# Arduino_Uno_Kit.net
KiCad netlist of a schematic drawn in Altium Designer
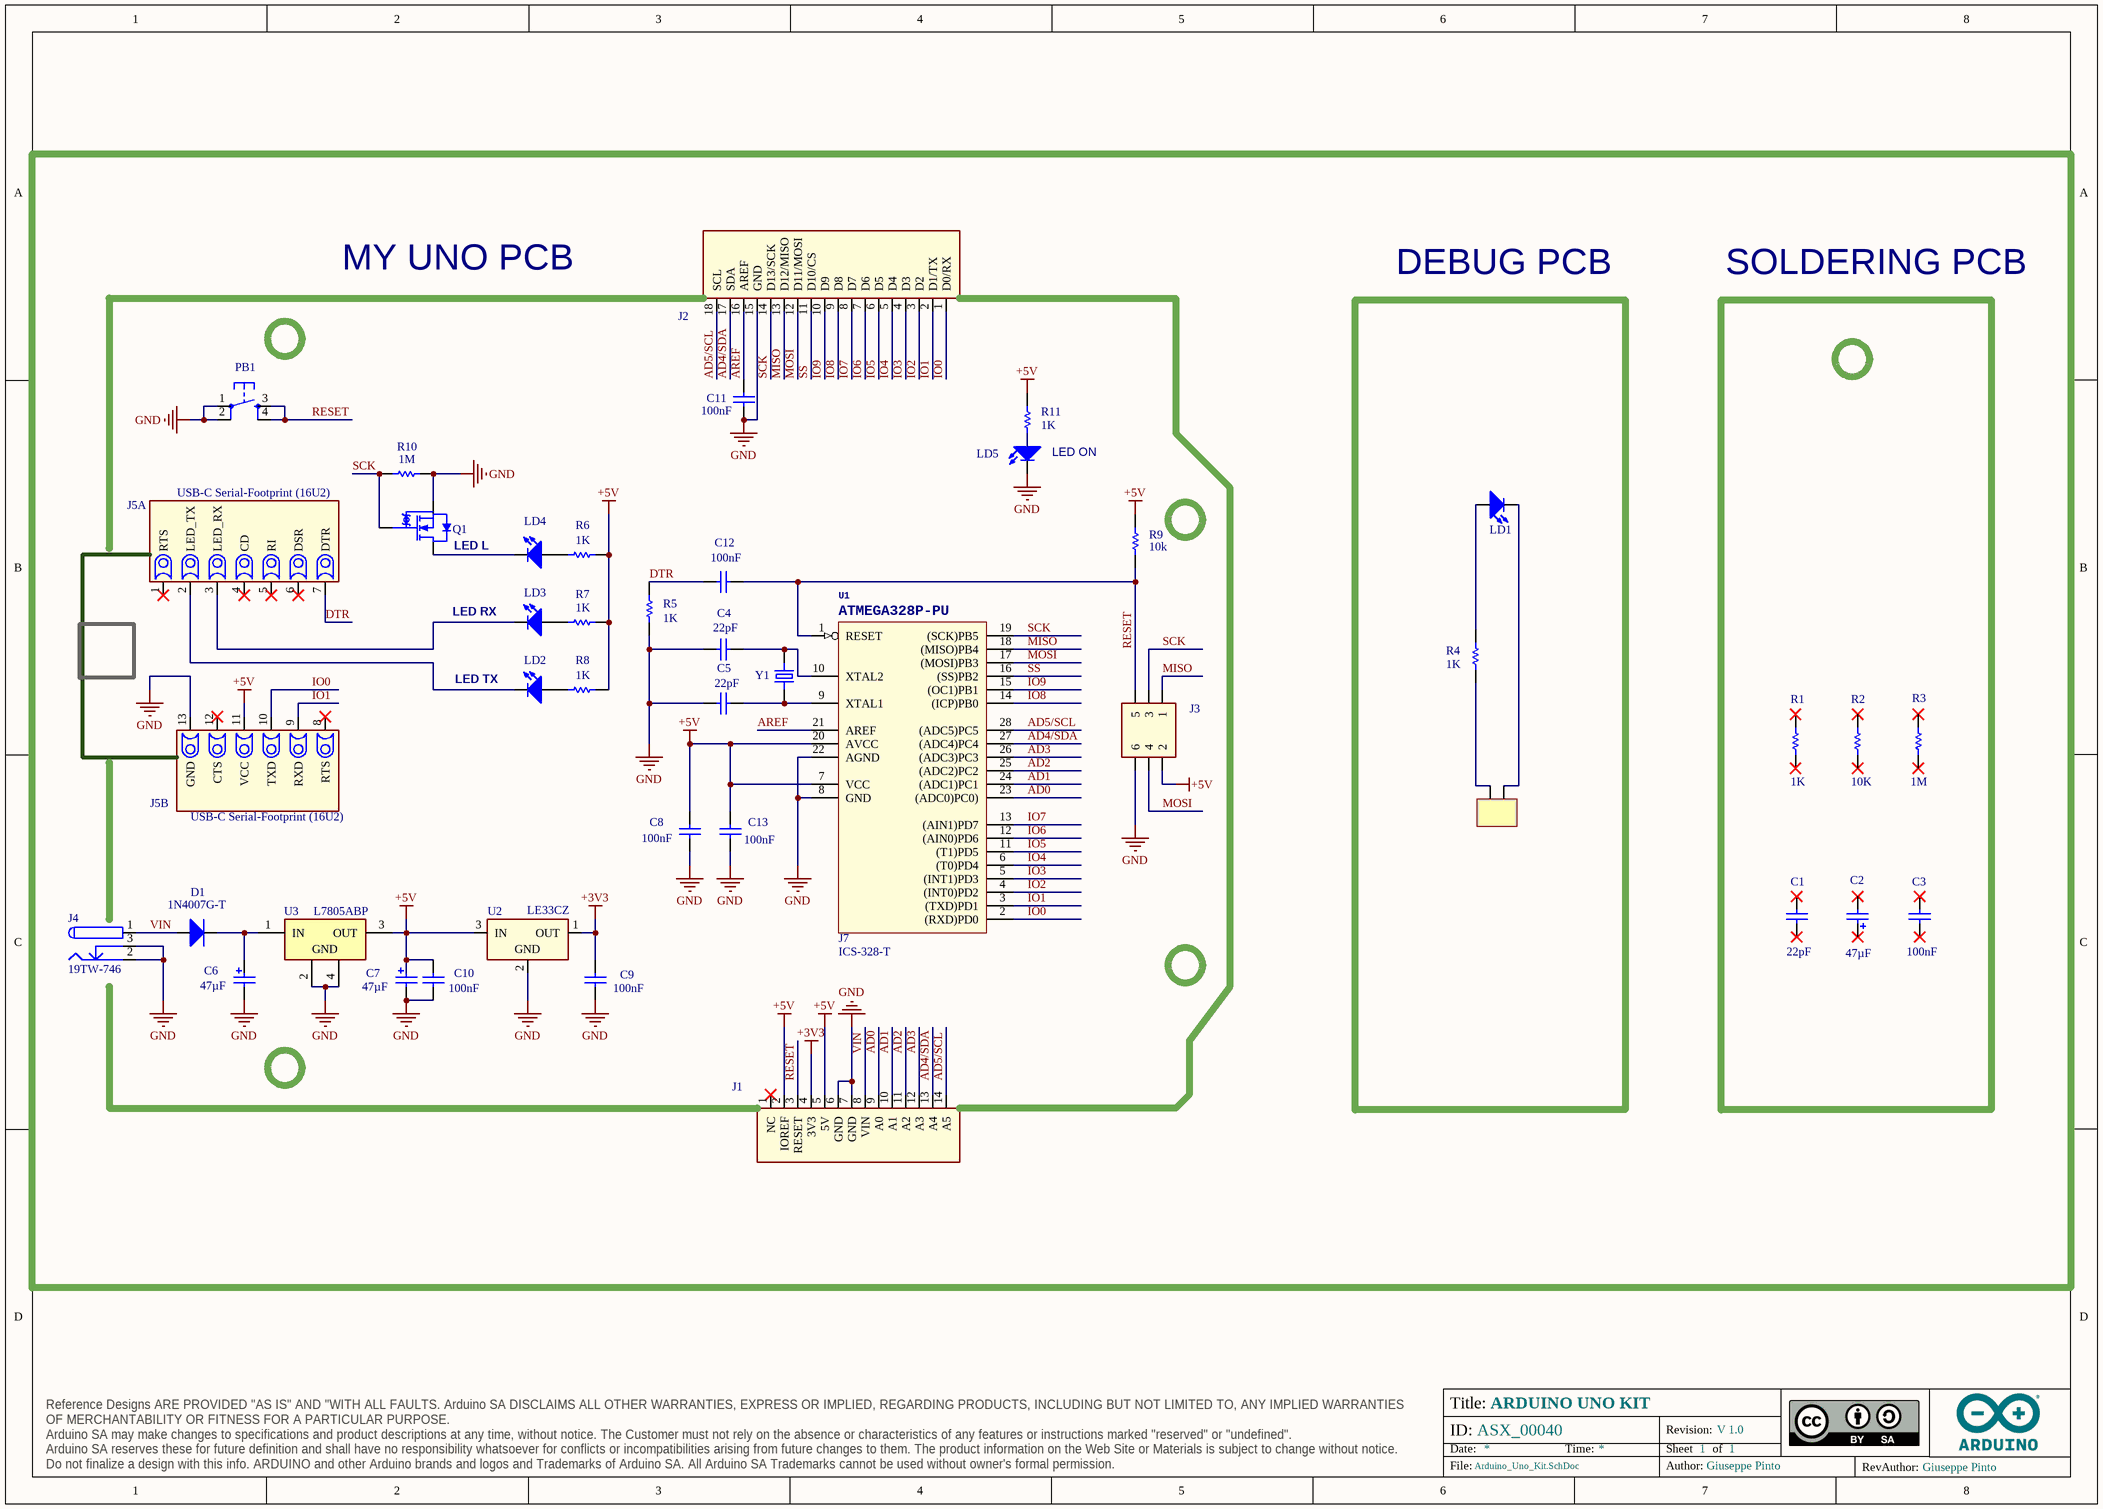
[diagram p0: Arduino_Uno_Kit.SchDoc]

(export (version "E")
  (design (tool "Eeschema 10.0.6"))
  (components
    (comp (ref "C1")
      (value "22pF")
      (footprint "TS170R1H220JSANB0R")
      (description "CAP THD 22pF 50V C0G 5%")
      (fields (field (name "PART NUMBER") "TS170R1H220JSANB0R") (field (name "MANUFACTURER") "Suntan"))
      (libsource (lib "Clean") (part "CAP"))
    )
    (comp (ref "C2")
      (value "47µF")
      (footprint "EKF476M1EE05TU")
      (description "CAP ALUM POL THD 47uF 25V")
      (fields (field (name "VOLTAGE") "25V") (field (name "PART NUMBER") "EKF476M1EE05TU"))
      (libsource (lib "Clean") (part "CAP-POL"))
    )
    (comp (ref "C3")
      (value "100nF")
      (footprint "B32529C0104J289")
      (description "CAP THD 100NF 63V POLIESTER")
      (fields (field (name "PART NUMBER") "B32529C0104J289") (field (name "MANUFACTURER") "EPCOS"))
      (libsource (lib "Clean") (part "CAP"))
    )
    (comp (ref "C4")
      (value "22pF")
      (footprint "TS170R1H220JSANB0R")
      (description "CAP THD 22pF 50V C0G 5%")
      (fields (field (name "PART NUMBER") "TS170R1H220JSANB0R") (field (name "MANUFACTURER") "Suntan"))
      (libsource (lib "Clean") (part "CAP"))
    )
    (comp (ref "C5")
      (value "22pF")
      (footprint "TS170R1H220JSANB0R")
      (description "CAP THD 22pF 50V C0G 5%")
      (fields (field (name "PART NUMBER") "TS170R1H220JSANB0R") (field (name "MANUFACTURER") "Suntan"))
      (libsource (lib "Clean") (part "CAP"))
    )
    (comp (ref "C6")
      (value "47µF")
      (footprint "EKF476M1EE05TU")
      (description "CAP ALUM POL THD 47uF 25V")
      (fields (field (name "VOLTAGE") "25V") (field (name "PART NUMBER") "EKF476M1EE05TU"))
      (libsource (lib "Clean") (part "CAP-POL"))
    )
    (comp (ref "C7")
      (value "47µF")
      (footprint "EKF476M1EE05TU")
      (description "CAP ALUM POL THD 47uF 25V")
      (fields (field (name "VOLTAGE") "25V") (field (name "PART NUMBER") "EKF476M1EE05TU"))
      (libsource (lib "Clean") (part "CAP-POL"))
    )
    (comp (ref "C8")
      (value "100nF")
      (footprint "B32529C0104J289")
      (description "CAP THD 100NF 63V POLIESTER")
      (fields (field (name "PART NUMBER") "B32529C0104J289") (field (name "MANUFACTURER") "EPCOS"))
      (libsource (lib "Clean") (part "CAP"))
    )
    (comp (ref "C9")
      (value "100nF")
      (footprint "B32529C0104J289")
      (description "CAP THD 100NF 63V POLIESTER")
      (fields (field (name "PART NUMBER") "B32529C0104J289") (field (name "MANUFACTURER") "EPCOS"))
      (libsource (lib "Clean") (part "CAP"))
    )
    (comp (ref "C10")
      (value "100nF")
      (footprint "B32529C0104J289")
      (description "CAP THD 100NF 63V POLIESTER")
      (fields (field (name "PART NUMBER") "B32529C0104J289") (field (name "MANUFACTURER") "EPCOS"))
      (libsource (lib "Clean") (part "CAP"))
    )
    (comp (ref "C11")
      (value "100nF")
      (footprint "B32529C0104J289")
      (description "CAP THD 100NF 63V POLIESTER")
      (fields (field (name "PART NUMBER") "B32529C0104J289") (field (name "MANUFACTURER") "EPCOS"))
      (libsource (lib "Clean") (part "CAP"))
    )
    (comp (ref "C12")
      (value "100nF")
      (footprint "B32529C0104J289")
      (description "CAP THD 100NF 63V POLIESTER")
      (fields (field (name "PART NUMBER") "B32529C0104J289") (field (name "MANUFACTURER") "EPCOS"))
      (libsource (lib "Clean") (part "CAP"))
    )
    (comp (ref "C13")
      (value "100nF")
      (footprint "B32529C0104J289")
      (description "CAP THD 100NF 63V POLIESTER")
      (fields (field (name "PART NUMBER") "B32529C0104J289") (field (name "MANUFACTURER") "EPCOS"))
      (libsource (lib "Clean") (part "CAP"))
    )
    (comp (ref "D1")
      (value "1N4007G-T")
      (footprint "1N4007G-T-Footprint-1")
      (description "Diodes [1N4007]")
      (fields (field (name "MANUFACTURER") "Panjit"))
      (libsource (lib "Clean") (part "1N4007G-T"))
    )
    (comp (ref "J1")
      (value "20TW-995")
      (footprint "1X14-CUSTOM")
      (description "CONN STRIP F/1/D 14v SER.NERA s1pin")
      (libsource (lib "Clean") (part "20TW-995"))
    )
    (comp (ref "J2")
      (value "20TW-994")
      (footprint "1X18-CUSTOM")
      (description "CONN STRIP F/1/D 18v SER.NERA s1pin")
      (libsource (lib "Clean") (part "20TW-994"))
    )
    (comp (ref "J3")
      (value "PH2-06-UA")
      (footprint "2X03")
      (description "CONN Header Through Hole 6 position 0.100\" (2.54mm)")
      (fields (field (name "MANUFACTURER") "Adam Tech"))
      (libsource (lib "Clean") (part "PH2-06-UA"))
    )
    (comp (ref "J4")
      (value "19TW-746")
      (footprint "POWERSUPPLY_DC-21MM")
      (description "CONN PWR JACK 2.1X5.5MM SOLDER")
      (fields (field (name "MANUFACTURER") "4UCON"))
      (libsource (lib "Clean") (part "19TW-746"))
    )
    (comp (ref "J5")
      (value "USB-C Serial-Footprint (16U2)")
      (footprint "USB-C Serial-Footprint (16U2)")
      (libsource (lib "Clean") (part "USB-C Serial CARRIER"))
    )
    (comp (ref "J6")
      (value "MK125002GO")
      (footprint "MK125002GO")
      (description "CONN MORS.CS 2v p3,5 10A aLING.VER")
      (fields (field (name "MANUFACTURER") "Adimpex"))
      (libsource (lib "Clean") (part "MK125002GO"))
    )
    (comp (ref "J7")
      (value "ICS-328-T")
      (footprint "ICS-328-T-Footprint-1")
      (description "CONN DIP 28 SOCKET")
      (fields (field (name "MANUFACTURER") "Adam Tech"))
      (libsource (lib "Clean") (part "CMP-003-0010-A.2"))
    )
    (comp (ref "LD1")
      (value "L-7104YD")
      (footprint "L314YD-Footprint-1")
      (description "LED THD YELLOW DIFFUSED T-1, 3mm")
      (fields (field (name "MANUFACTURER") "Kingbright"))
      (libsource (lib "Clean") (part "LED"))
    )
    (comp (ref "LD2")
      (value "L-7104YD")
      (footprint "L314YD-Footprint-1")
      (description "LED THD YELLOW DIFFUSED T-1, 3mm")
      (fields (field (name "MANUFACTURER") "Kingbright"))
      (libsource (lib "Clean") (part "LED"))
    )
    (comp (ref "LD3")
      (value "L-7104YD")
      (footprint "L314YD-Footprint-1")
      (description "LED THD YELLOW DIFFUSED T-1, 3mm")
      (fields (field (name "MANUFACTURER") "Kingbright"))
      (libsource (lib "Clean") (part "LED"))
    )
    (comp (ref "LD4")
      (value "L-7104YD")
      (footprint "L314YD-Footprint-1")
      (description "LED THD YELLOW DIFFUSED T-1, 3mm")
      (fields (field (name "MANUFACTURER") "Kingbright"))
      (libsource (lib "Clean") (part "LED"))
    )
    (comp (ref "LD5")
      (value "L-7104GD")
      (footprint "L314YD-Footprint-1")
      (description "LED THD GREEN DIFFUSED T-1, 3mm")
      (fields (field (name "MANUFACTURER") "Kingbright"))
      (libsource (lib "Clean") (part "LED"))
    )
    (comp (ref "PB1")
      (value "TS21043-160B-5227260")
      (footprint "SW6X6")
      (description "PUSHBUTTON.6x6 CS Hatt0,7 NERO 160g")
      (libsource (lib "Clean") (part "PB-TE"))
    )
    (comp (ref "Q1")
      (value "2N7000BU")
      (footprint "SOT23")
      (description "TRANSISTOR NMOS SMALL SIGNAL EFFECT 0.2A I(D) 1-ELEMENT")
      (fields (field (name "MANUFACTURER") "Onsemi"))
      (libsource (lib "Clean") (part "NMOS-2"))
    )
    (comp (ref "R1")
      (value "1K")
      (footprint "A5215")
      (description "RES FIXED THD 1K OHM 1/4W 5%")
      (fields (field (name "TOLERANCE") "5%") (field (name "POWER") "250mW"))
      (libsource (lib "Clean") (part "RES"))
    )
    (comp (ref "R2")
      (value "10K")
      (footprint "A5213")
      (description "RES THD 10K 1/4W 5%")
      (fields (field (name "TOLERANCE") "5%") (field (name "POWER") "250mW"))
      (libsource (lib "Clean") (part "RES"))
    )
    (comp (ref "R3")
      (value "1M")
      (footprint "A5217")
      (description "RES THD 1M OHM 1/4w  5%")
      (fields (field (name "TOLERANCE") "5%") (field (name "POWER") "250mW"))
      (libsource (lib "Clean") (part "RES"))
    )
    (comp (ref "R4")
      (value "1K")
      (footprint "A5215")
      (description "RES FIXED THD 1K OHM 1/4W 5%")
      (fields (field (name "TOLERANCE") "5%") (field (name "POWER") "250mW"))
      (libsource (lib "Clean") (part "RES"))
    )
    (comp (ref "R5")
      (value "1K")
      (footprint "A5215")
      (description "RES FIXED THD 1K OHM 1/4W 5%")
      (fields (field (name "TOLERANCE") "5%") (field (name "POWER") "250mW"))
      (libsource (lib "Clean") (part "RES"))
    )
    (comp (ref "R6")
      (value "1K")
      (footprint "A5215")
      (description "RES FIXED THD 1K OHM 1/4W 5%")
      (fields (field (name "TOLERANCE") "5%") (field (name "POWER") "250mW"))
      (libsource (lib "Clean") (part "RES"))
    )
    (comp (ref "R7")
      (value "1K")
      (footprint "A5215")
      (description "RES FIXED THD 1K OHM 1/4W 5%")
      (fields (field (name "TOLERANCE") "5%") (field (name "POWER") "250mW"))
      (libsource (lib "Clean") (part "RES"))
    )
    (comp (ref "R8")
      (value "1K")
      (footprint "A5215")
      (description "RES FIXED THD 1K OHM 1/4W 5%")
      (fields (field (name "TOLERANCE") "5%") (field (name "POWER") "250mW"))
      (libsource (lib "Clean") (part "RES"))
    )
    (comp (ref "R9")
      (value "10k")
      (footprint "A5213")
      (description "RES THD 10K 1/4W 5%")
      (fields (field (name "TOLERANCE") "5%") (field (name "POWER") "250mW"))
      (libsource (lib "Clean") (part "RES"))
    )
    (comp (ref "R10")
      (value "1M")
      (footprint "A5217")
      (description "RES THD 1M OHM 1/4w  5%")
      (fields (field (name "TOLERANCE") "5%") (field (name "POWER") "250mW"))
      (libsource (lib "Clean") (part "RES"))
    )
    (comp (ref "R11")
      (value "1K")
      (footprint "A5215")
      (description "RES FIXED THD 1K OHM 1/4W 5%")
      (fields (field (name "TOLERANCE") "5%") (field (name "POWER") "250mW"))
      (libsource (lib "Clean") (part "RES"))
    )
    (comp (ref "U1")
      (value "ATMEGA328P-PU")
      (footprint "DIL28-3")
      (description "IC MICROCONTROLLER ATMEGA328P-PU")
      (fields (field (name "MANUFACTURER") "Microchip"))
      (libsource (lib "Clean") (part "ATMEGA328P-PU-A.6"))
    )
    (comp (ref "U2")
      (value "LE33CZ")
      (footprint "LE33CZ-TR/AP")
      (description "IC REG LDO FIXED 3.3V, 0.2V DROPOUT TO-92-3")
      (fields (field (name "PART NUMBER") "LE33CZ-TR/AP") (field (name "MANUFACTURER") "STMicroelectronics"))
      (libsource (lib "Clean") (part "LE33CZ-TR/AP"))
    )
    (comp (ref "U3")
      (value "L7805ABP")
      (footprint "TO220")
      (description "IC REG LINEAR 5V 1.5A TO220AB")
      (fields (field (name "MANUFACTURER") "STMicroelectronics") (field (name "TOLERANCE") "5%"))
      (libsource (lib "Clean") (part "L7805CT"))
    )
    (comp (ref "Y1")
      (value "ECS-160-20-4X-DU")
      (footprint "ECS-160-20-4X-DU-Footprint-1")
      (description "CRYSTAL 16.0000MHZ 20PF THD")
      (fields (field (name "MANUFACTURER") "ECS"))
      (libsource (lib "Clean") (part "Crystal"))
    )
  )
  (nets
    (net (code "1") (name "+3V3") (class "Default")
      (node (ref "C9") (pin "1") (pinfunction "1_1") (pintype "passive"))
      (node (ref "J1") (pin "4") (pinfunction "3V3_4") (pintype "passive"))
      (node (ref "U2") (pin "1") (pinfunction "OUT_1") (pintype "power_in"))
    )
    (net (code "2") (name "+5V") (class "Default")
      (node (ref "C10") (pin "1") (pinfunction "1_1") (pintype "passive"))
      (node (ref "C13") (pin "1") (pinfunction "1_1") (pintype "passive"))
      (node (ref "C7") (pin "2") (pinfunction "2_2") (pintype "passive"))
      (node (ref "C8") (pin "1") (pinfunction "1_1") (pintype "passive"))
      (node (ref "J1") (pin "2") (pinfunction "IOREF_2") (pintype "passive"))
      (node (ref "J1") (pin "5") (pinfunction "5V_5") (pintype "passive"))
      (node (ref "J3") (pin "2") (pinfunction "2_2") (pintype "passive"))
      (node (ref "J5") (pin "11") (pinfunction "VCC_11") (pintype "passive"))
      (node (ref "R11") (pin "1") (pinfunction "1_1") (pintype "passive"))
      (node (ref "R6") (pin "1") (pinfunction "1_1") (pintype "passive"))
      (node (ref "R7") (pin "1") (pinfunction "1_1") (pintype "passive"))
      (node (ref "R8") (pin "1") (pinfunction "1_1") (pintype "passive"))
      (node (ref "R9") (pin "2") (pinfunction "2_2") (pintype "passive"))
      (node (ref "U1") (pin "20") (pinfunction "AVCC_20") (pintype "power_in"))
      (node (ref "U1") (pin "7") (pinfunction "VCC_7") (pintype "power_in"))
      (node (ref "U2") (pin "3") (pinfunction "IN_3") (pintype "power_in"))
      (node (ref "U3") (pin "3") (pinfunction "OUT_3") (pintype "power_in"))
    )
    (net (code "3") (name "/AD0") (class "Default")
      (node (ref "J1") (pin "9") (pinfunction "A0_9") (pintype "passive"))
      (node (ref "U1") (pin "23") (pinfunction "(ADC0)PC0)_23") (pintype "passive"))
    )
    (net (code "4") (name "/AD1") (class "Default")
      (node (ref "J1") (pin "10") (pinfunction "A1_10") (pintype "passive"))
      (node (ref "U1") (pin "24") (pinfunction "(ADC1)PC1_24") (pintype "passive"))
    )
    (net (code "5") (name "/AD2") (class "Default")
      (node (ref "J1") (pin "11") (pinfunction "A2_11") (pintype "passive"))
      (node (ref "U1") (pin "25") (pinfunction "(ADC2)PC2_25") (pintype "passive"))
    )
    (net (code "6") (name "/AD3") (class "Default")
      (node (ref "J1") (pin "12") (pinfunction "A3_12") (pintype "passive"))
      (node (ref "U1") (pin "26") (pinfunction "(ADC3)PC3_26") (pintype "passive"))
    )
    (net (code "7") (name "/AD4{slash}SDA") (class "Default")
      (node (ref "J1") (pin "13") (pinfunction "A4_13") (pintype "passive"))
      (node (ref "J2") (pin "17") (pinfunction "SDA_17") (pintype "passive"))
      (node (ref "U1") (pin "27") (pinfunction "(ADC4)PC4_27") (pintype "passive"))
    )
    (net (code "8") (name "/AD5{slash}SCL") (class "Default")
      (node (ref "J1") (pin "14") (pinfunction "A5_14") (pintype "passive"))
      (node (ref "J2") (pin "18") (pinfunction "SCL_18") (pintype "passive"))
      (node (ref "U1") (pin "28") (pinfunction "(ADC5)PC5_28") (pintype "passive"))
    )
    (net (code "9") (name "/AREF") (class "Default")
      (node (ref "C11") (pin "1") (pinfunction "1_1") (pintype "passive"))
      (node (ref "J2") (pin "16") (pinfunction "AREF_16") (pintype "passive"))
      (node (ref "U1") (pin "21") (pinfunction "AREF_21") (pintype "passive"))
    )
    (net (code "10") (name "/DTR") (class "Default")
      (node (ref "C12") (pin "2") (pinfunction "2_2") (pintype "passive"))
      (node (ref "J5") (pin "7") (pinfunction "DTR_7") (pintype "passive"))
      (node (ref "R5") (pin "1") (pinfunction "1_1") (pintype "passive"))
    )
    (net (code "11") (name "/IO0") (class "Default")
      (node (ref "J2") (pin "1") (pinfunction "D0/RX_1") (pintype "passive"))
      (node (ref "J5") (pin "10") (pinfunction "TXD_10") (pintype "passive"))
      (node (ref "U1") (pin "2") (pinfunction "(RXD)PD0_2") (pintype "passive"))
    )
    (net (code "12") (name "/IO1") (class "Default")
      (node (ref "J2") (pin "2") (pinfunction "D1/TX_2") (pintype "passive"))
      (node (ref "J5") (pin "9") (pinfunction "RXD_9") (pintype "passive"))
      (node (ref "U1") (pin "3") (pinfunction "(TXD)PD1_3") (pintype "passive"))
    )
    (net (code "13") (name "/IO2") (class "Default")
      (node (ref "J2") (pin "3") (pinfunction "D2_3") (pintype "passive"))
      (node (ref "U1") (pin "4") (pinfunction "(INT0)PD2_4") (pintype "passive"))
    )
    (net (code "14") (name "/IO3") (class "Default")
      (node (ref "J2") (pin "4") (pinfunction "D3_4") (pintype "passive"))
      (node (ref "U1") (pin "5") (pinfunction "(INT1)PD3_5") (pintype "passive"))
    )
    (net (code "15") (name "/IO4") (class "Default")
      (node (ref "J2") (pin "5") (pinfunction "D4_5") (pintype "passive"))
      (node (ref "U1") (pin "6") (pinfunction "(T0)PD4_6") (pintype "passive"))
    )
    (net (code "16") (name "/IO5") (class "Default")
      (node (ref "J2") (pin "6") (pinfunction "D5_6") (pintype "passive"))
      (node (ref "U1") (pin "11") (pinfunction "(T1)PD5_11") (pintype "passive"))
    )
    (net (code "17") (name "/IO6") (class "Default")
      (node (ref "J2") (pin "7") (pinfunction "D6_7") (pintype "passive"))
      (node (ref "U1") (pin "12") (pinfunction "(AIN0)PD6_12") (pintype "passive"))
    )
    (net (code "18") (name "/IO7") (class "Default")
      (node (ref "J2") (pin "8") (pinfunction "D7_8") (pintype "passive"))
      (node (ref "U1") (pin "13") (pinfunction "(AIN1)PD7_13") (pintype "passive"))
    )
    (net (code "19") (name "/IO8") (class "Default")
      (node (ref "J2") (pin "9") (pinfunction "D8_9") (pintype "passive"))
      (node (ref "U1") (pin "14") (pinfunction "(ICP)PB0_14") (pintype "passive"))
    )
    (net (code "20") (name "/IO9") (class "Default")
      (node (ref "J2") (pin "10") (pinfunction "D9_10") (pintype "passive"))
      (node (ref "U1") (pin "15") (pinfunction "(OC1)PB1_15") (pintype "passive"))
    )
    (net (code "21") (name "/MISO") (class "Default")
      (node (ref "J2") (pin "13") (pinfunction "D12/MISO_13") (pintype "passive"))
      (node (ref "J3") (pin "1") (pinfunction "1_1") (pintype "passive"))
      (node (ref "U1") (pin "18") (pinfunction "(MISO)PB4_18") (pintype "passive"))
    )
    (net (code "22") (name "/MOSI") (class "Default")
      (node (ref "J2") (pin "12") (pinfunction "D11/MOSI_12") (pintype "passive"))
      (node (ref "J3") (pin "4") (pinfunction "4_4") (pintype "passive"))
      (node (ref "U1") (pin "17") (pinfunction "(MOSI)PB3_17") (pintype "passive"))
    )
    (net (code "23") (name "/RESET") (class "Default")
      (node (ref "C12") (pin "1") (pinfunction "1_1") (pintype "passive"))
      (node (ref "J1") (pin "3") (pinfunction "RESET_3") (pintype "passive"))
      (node (ref "J3") (pin "5") (pinfunction "5_5") (pintype "passive"))
      (node (ref "PB1") (pin "3") (pinfunction "3_3") (pintype "passive"))
      (node (ref "PB1") (pin "4") (pinfunction "4_4") (pintype "passive"))
      (node (ref "R9") (pin "1") (pinfunction "1_1") (pintype "passive"))
      (node (ref "U1") (pin "1") (pinfunction "RESET_1") (pintype "input"))
    )
    (net (code "24") (name "/SCK") (class "Default")
      (node (ref "J2") (pin "14") (pinfunction "D13/SCK_14") (pintype "passive"))
      (node (ref "J3") (pin "3") (pinfunction "3_3") (pintype "passive"))
      (node (ref "Q1") (pin "2") (pinfunction "G_2") (pintype "passive"))
      (node (ref "R10") (pin "1") (pinfunction "1_1") (pintype "passive"))
      (node (ref "U1") (pin "19") (pinfunction "(SCK)PB5_19") (pintype "passive"))
    )
    (net (code "25") (name "/SS") (class "Default")
      (node (ref "J2") (pin "11") (pinfunction "D10/CS_11") (pintype "passive"))
      (node (ref "U1") (pin "16") (pinfunction "(SS)PB2_16") (pintype "passive"))
    )
    (net (code "26") (name "/VIN") (class "Default")
      (node (ref "D1") (pin "1") (pinfunction "1_1") (pintype "passive"))
      (node (ref "J1") (pin "8") (pinfunction "VIN_8") (pintype "passive"))
      (node (ref "J4") (pin "1") (pinfunction "1_1") (pintype "power_in"))
    )
    (net (code "27") (name "GND") (class "Default")
      (node (ref "C10") (pin "2") (pinfunction "2_2") (pintype "passive"))
      (node (ref "C11") (pin "2") (pinfunction "2_2") (pintype "passive"))
      (node (ref "C13") (pin "2") (pinfunction "2_2") (pintype "passive"))
      (node (ref "C4") (pin "2") (pinfunction "2_2") (pintype "passive"))
      (node (ref "C5") (pin "2") (pinfunction "2_2") (pintype "passive"))
      (node (ref "C6") (pin "1") (pinfunction "1_1") (pintype "passive"))
      (node (ref "C7") (pin "1") (pinfunction "1_1") (pintype "passive"))
      (node (ref "C8") (pin "2") (pinfunction "2_2") (pintype "passive"))
      (node (ref "C9") (pin "2") (pinfunction "2_2") (pintype "passive"))
      (node (ref "J1") (pin "6") (pinfunction "GND_6") (pintype "passive"))
      (node (ref "J1") (pin "7") (pinfunction "GND_7") (pintype "passive"))
      (node (ref "J2") (pin "15") (pinfunction "GND_15") (pintype "passive"))
      (node (ref "J3") (pin "6") (pinfunction "6_6") (pintype "passive"))
      (node (ref "J4") (pin "2") (pinfunction "2_2") (pintype "power_in"))
      (node (ref "J4") (pin "3") (pinfunction "3_3") (pintype "power_in"))
      (node (ref "J5") (pin "13") (pinfunction "GND_13") (pintype "passive"))
      (node (ref "LD5") (pin "C") (pinfunction "C_C") (pintype "passive"))
      (node (ref "PB1") (pin "1") (pinfunction "1_1") (pintype "passive"))
      (node (ref "PB1") (pin "2") (pinfunction "2_2") (pintype "passive"))
      (node (ref "Q1") (pin "1") (pinfunction "S_1") (pintype "passive"))
      (node (ref "R10") (pin "2") (pinfunction "2_2") (pintype "passive"))
      (node (ref "R5") (pin "2") (pinfunction "2_2") (pintype "passive"))
      (node (ref "U1") (pin "22") (pinfunction "AGND_22") (pintype "power_in"))
      (node (ref "U1") (pin "8") (pinfunction "GND_8") (pintype "power_in"))
      (node (ref "U2") (pin "2") (pinfunction "GND_2") (pintype "power_in"))
      (node (ref "U3") (pin "2") (pinfunction "GND_2") (pintype "power_in"))
      (node (ref "U3") (pin "4") (pinfunction "GND_4") (pintype "power_in"))
    )
    (net (code "28") (name "Net-(J5A-LED_RX)") (class "Default")
      (node (ref "J5") (pin "3") (pinfunction "LED_RX_3") (pintype "passive"))
      (node (ref "LD3") (pin "C") (pinfunction "C_C") (pintype "passive"))
    )
    (net (code "29") (name "Net-(J5A-LED_TX)") (class "Default")
      (node (ref "J5") (pin "2") (pinfunction "LED_TX_2") (pintype "passive"))
      (node (ref "LD2") (pin "C") (pinfunction "C_C") (pintype "passive"))
    )
    (net (code "30") (name "Net-(J6-Pad1)") (class "Default")
      (node (ref "J6") (pin "1") (pinfunction "1_1") (pintype "passive"))
      (node (ref "R4") (pin "1") (pinfunction "1_1") (pintype "passive"))
    )
    (net (code "31") (name "Net-(J6-Pad2)") (class "Default")
      (node (ref "J6") (pin "2") (pinfunction "2_2") (pintype "passive"))
      (node (ref "LD1") (pin "C") (pinfunction "C_C") (pintype "passive"))
    )
    (net (code "32") (name "Net-(LD1-PadA)") (class "Default")
      (node (ref "LD1") (pin "A") (pinfunction "A_A") (pintype "passive"))
      (node (ref "R4") (pin "2") (pinfunction "2_2") (pintype "passive"))
    )
    (net (code "33") (name "Net-(LD2-PadA)") (class "Default")
      (node (ref "LD2") (pin "A") (pinfunction "A_A") (pintype "passive"))
      (node (ref "R8") (pin "2") (pinfunction "2_2") (pintype "passive"))
    )
    (net (code "34") (name "Net-(LD3-PadA)") (class "Default")
      (node (ref "LD3") (pin "A") (pinfunction "A_A") (pintype "passive"))
      (node (ref "R7") (pin "2") (pinfunction "2_2") (pintype "passive"))
    )
    (net (code "35") (name "Net-(LD4-PadA)") (class "Default")
      (node (ref "LD4") (pin "A") (pinfunction "A_A") (pintype "passive"))
      (node (ref "R6") (pin "2") (pinfunction "2_2") (pintype "passive"))
    )
    (net (code "36") (name "Net-(LD5-PadA)") (class "Default")
      (node (ref "LD5") (pin "A") (pinfunction "A_A") (pintype "passive"))
      (node (ref "R11") (pin "2") (pinfunction "2_2") (pintype "passive"))
    )
    (net (code "37") (name "Net-(Q1-D)") (class "Default")
      (node (ref "LD4") (pin "C") (pinfunction "C_C") (pintype "passive"))
      (node (ref "Q1") (pin "3") (pinfunction "D_3") (pintype "passive"))
    )
    (net (code "38") (name "Net-(U1-XTAL1)") (class "Default")
      (node (ref "C5") (pin "1") (pinfunction "1_1") (pintype "passive"))
      (node (ref "U1") (pin "9") (pinfunction "XTAL1_9") (pintype "passive"))
      (node (ref "Y1") (pin "1") (pinfunction "1_1") (pintype "passive"))
    )
    (net (code "39") (name "Net-(U1-XTAL2)") (class "Default")
      (node (ref "C4") (pin "1") (pinfunction "1_1") (pintype "passive"))
      (node (ref "U1") (pin "10") (pinfunction "XTAL2_10") (pintype "passive"))
      (node (ref "Y1") (pin "2") (pinfunction "2_2") (pintype "passive"))
    )
    (net (code "40") (name "Net-(U3-IN)") (class "Default")
      (node (ref "C6") (pin "2") (pinfunction "2_2") (pintype "passive"))
      (node (ref "D1") (pin "2") (pinfunction "2_2") (pintype "passive"))
      (node (ref "U3") (pin "1") (pinfunction "IN_1") (pintype "power_in"))
    )
    (net (code "41") (name "unconnected-(C1-Pad1)") (class "Default")
      (node (ref "C1") (pin "1") (pinfunction "1_1") (pintype "passive+no_connect"))
    )
    (net (code "42") (name "unconnected-(C1-Pad2)") (class "Default")
      (node (ref "C1") (pin "2") (pinfunction "2_2") (pintype "passive+no_connect"))
    )
    (net (code "43") (name "unconnected-(C2-Pad1)") (class "Default")
      (node (ref "C2") (pin "1") (pinfunction "1_1") (pintype "passive+no_connect"))
    )
    (net (code "44") (name "unconnected-(C2-Pad2)") (class "Default")
      (node (ref "C2") (pin "2") (pinfunction "2_2") (pintype "passive+no_connect"))
    )
    (net (code "45") (name "unconnected-(C3-Pad1)") (class "Default")
      (node (ref "C3") (pin "1") (pinfunction "1_1") (pintype "passive+no_connect"))
    )
    (net (code "46") (name "unconnected-(C3-Pad2)") (class "Default")
      (node (ref "C3") (pin "2") (pinfunction "2_2") (pintype "passive+no_connect"))
    )
    (net (code "47") (name "unconnected-(J1-NC-Pad1)") (class "Default")
      (node (ref "J1") (pin "1") (pinfunction "NC_1") (pintype "passive+no_connect"))
    )
    (net (code "48") (name "unconnected-(J5A-CD-Pad4)") (class "Default")
      (node (ref "J5") (pin "4") (pinfunction "CD_4") (pintype "passive+no_connect"))
    )
    (net (code "49") (name "unconnected-(J5A-DSR-Pad6)") (class "Default")
      (node (ref "J5") (pin "6") (pinfunction "DSR_6") (pintype "passive+no_connect"))
    )
    (net (code "50") (name "unconnected-(J5A-RI-Pad5)") (class "Default")
      (node (ref "J5") (pin "5") (pinfunction "RI_5") (pintype "passive+no_connect"))
    )
    (net (code "51") (name "unconnected-(J5A-RTS-Pad1)") (class "Default")
      (node (ref "J5") (pin "1") (pinfunction "RTS_1") (pintype "passive+no_connect"))
    )
    (net (code "52") (name "unconnected-(J5B-CTS-Pad12)") (class "Default")
      (node (ref "J5") (pin "12") (pinfunction "CTS_12") (pintype "passive+no_connect"))
    )
    (net (code "53") (name "unconnected-(J5B-RTS-Pad8)") (class "Default")
      (node (ref "J5") (pin "8") (pinfunction "RTS_8") (pintype "passive+no_connect"))
    )
    (net (code "54") (name "unconnected-(R1-Pad1)") (class "Default")
      (node (ref "R1") (pin "1") (pinfunction "1_1") (pintype "passive+no_connect"))
    )
    (net (code "55") (name "unconnected-(R1-Pad2)") (class "Default")
      (node (ref "R1") (pin "2") (pinfunction "2_2") (pintype "passive+no_connect"))
    )
    (net (code "56") (name "unconnected-(R2-Pad1)") (class "Default")
      (node (ref "R2") (pin "1") (pinfunction "1_1") (pintype "passive+no_connect"))
    )
    (net (code "57") (name "unconnected-(R2-Pad2)") (class "Default")
      (node (ref "R2") (pin "2") (pinfunction "2_2") (pintype "passive+no_connect"))
    )
    (net (code "58") (name "unconnected-(R3-Pad1)") (class "Default")
      (node (ref "R3") (pin "1") (pinfunction "1_1") (pintype "passive+no_connect"))
    )
    (net (code "59") (name "unconnected-(R3-Pad2)") (class "Default")
      (node (ref "R3") (pin "2") (pinfunction "2_2") (pintype "passive+no_connect"))
    )
  )
)
